# HW2schem.net
KiCad netlist of a schematic drawn in EAGLE
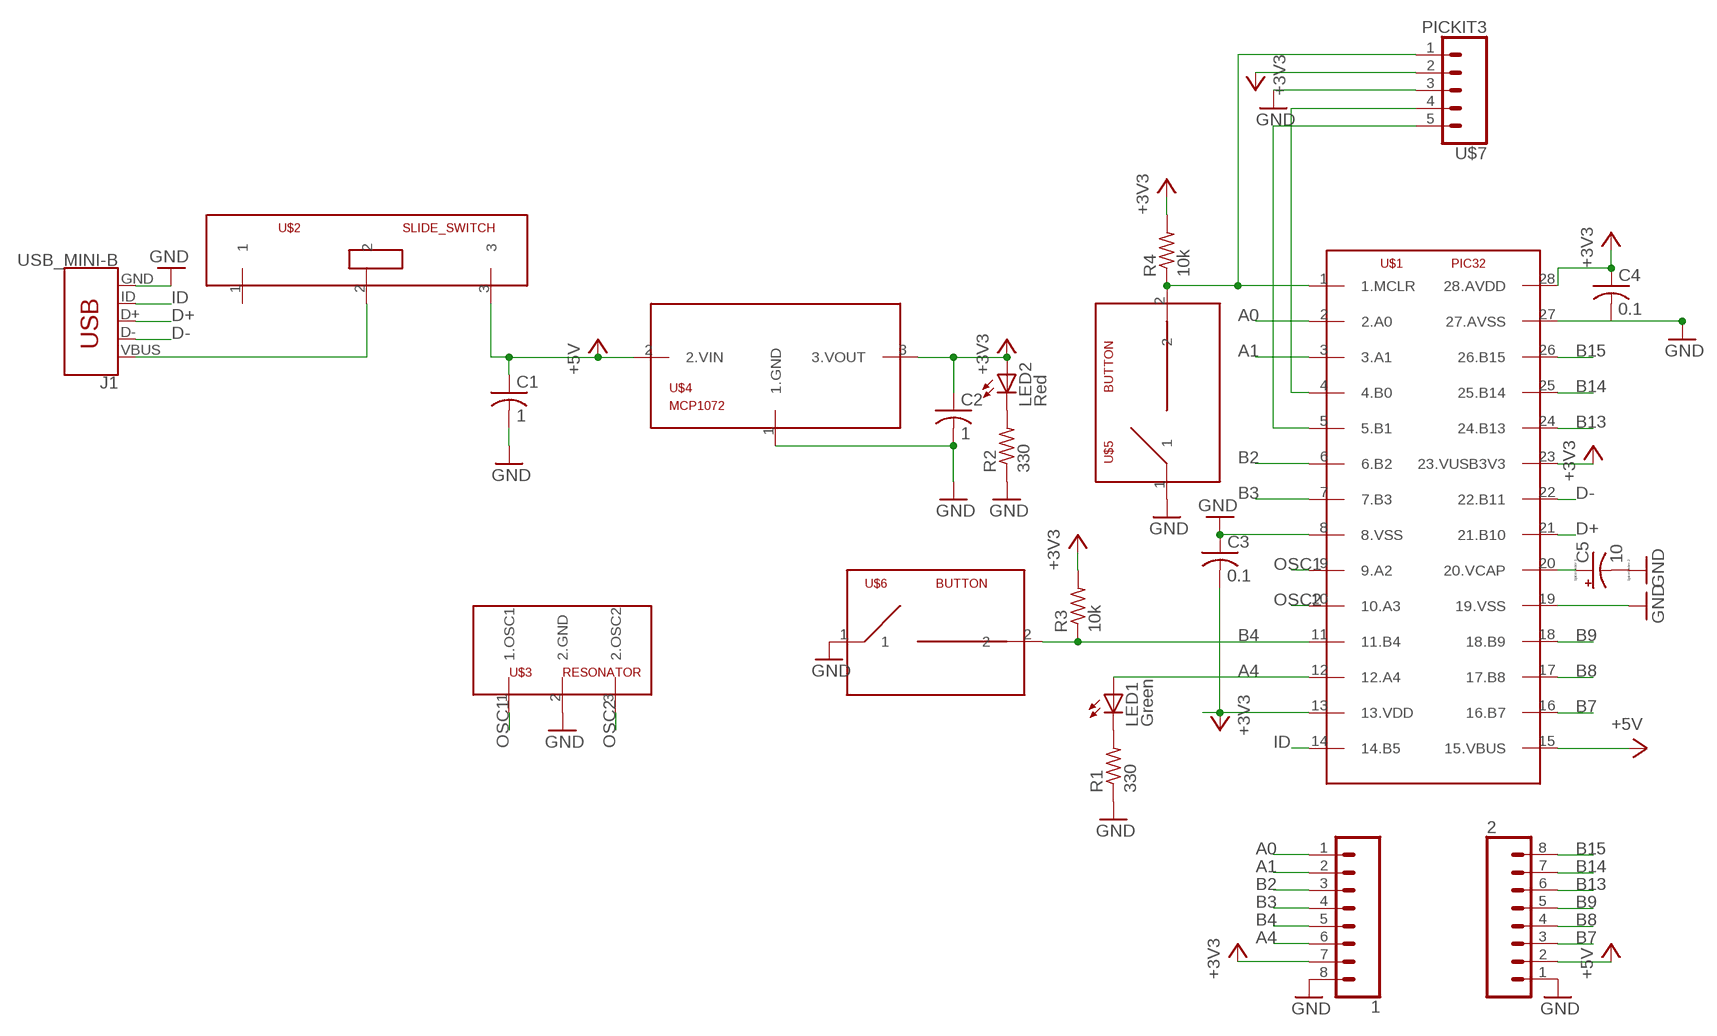
[diagram p0: schematic, sheet 1]

(export (version "E")
  (design (tool "Eeschema 10.0.6"))
  (components
    (comp (ref "1")
      (value "CONN_08NO_SILK_FEMALE_PTH")
      (footprint "eagle-import:1X08_NO_SILK")
      (libsource (lib "eagle-import") (part "CONN_08NO_SILK_FEMALE_PTH"))
    )
    (comp (ref "2")
      (value "CONN_08NO_SILK_FEMALE_PTH")
      (footprint "eagle-import:1X08_NO_SILK")
      (libsource (lib "eagle-import") (part "CONN_08NO_SILK_FEMALE_PTH"))
    )
    (comp (ref "C1")
      (value "1")
      (footprint "eagle-import:C025-024X044")
      (libsource (lib "eagle-import") (part "C-US025-024X044"))
    )
    (comp (ref "C2")
      (value "1")
      (footprint "eagle-import:C025-024X044")
      (libsource (lib "eagle-import") (part "C-US025-024X044"))
    )
    (comp (ref "C3")
      (value "0.1")
      (footprint "eagle-import:C025-024X044")
      (libsource (lib "eagle-import") (part "C-US025-024X044"))
    )
    (comp (ref "C4")
      (value "0.1")
      (footprint "eagle-import:C025-024X044")
      (libsource (lib "eagle-import") (part "C-US025-024X044"))
    )
    (comp (ref "C5")
      (value "10")
      (footprint "eagle-import:B45181A")
      (libsource (lib "eagle-import") (part "CPOL-USB45181A"))
    )
    (comp (ref "J1")
      (value "USB_MINI-B")
      (footprint "eagle-import:USB-MB-H")
      (libsource (lib "eagle-import") (part "USB_MINI-B"))
    )
    (comp (ref "LED1")
      (value "Green")
      (footprint "eagle-import:LED3MM")
      (libsource (lib "eagle-import") (part "LED3MM"))
    )
    (comp (ref "LED2")
      (value "Red")
      (footprint "eagle-import:LED3MM")
      (libsource (lib "eagle-import") (part "LED3MM"))
    )
    (comp (ref "R1")
      (value "330")
      (footprint "eagle-import:0204_7")
      (libsource (lib "eagle-import") (part "R-US_0204/7"))
    )
    (comp (ref "R2")
      (value "330")
      (footprint "eagle-import:0204_7")
      (libsource (lib "eagle-import") (part "R-US_0204/7"))
    )
    (comp (ref "R3")
      (value "10k")
      (footprint "eagle-import:0204_7")
      (libsource (lib "eagle-import") (part "R-US_0204/7"))
    )
    (comp (ref "R4")
      (value "10k")
      (footprint "eagle-import:0204_7")
      (libsource (lib "eagle-import") (part "R-US_0204/7"))
    )
    (comp (ref "U$1")
      (value "PIC32")
      (footprint "eagle-import:DIL28-3")
      (libsource (lib "eagle-import") (part "PIC32"))
    )
    (comp (ref "U$2")
      (value "SLIDE_SWITCH")
      (footprint "eagle-import:SLIDE_SWITCH")
      (libsource (lib "eagle-import") (part "SLIDE_SWITCH"))
    )
    (comp (ref "U$3")
      (value "RESONATOR")
      (footprint "eagle-import:RESONATOR")
      (libsource (lib "eagle-import") (part "RESONATOR"))
    )
    (comp (ref "U$4")
      (value "MCP1072")
      (footprint "eagle-import:TO92")
      (libsource (lib "eagle-import") (part "MCP1072"))
    )
    (comp (ref "U$5")
      (value "BUTTON")
      (footprint "eagle-import:BUTTON")
      (libsource (lib "eagle-import") (part "BUTTON"))
    )
    (comp (ref "U$6")
      (value "BUTTON")
      (footprint "eagle-import:BUTTON")
      (libsource (lib "eagle-import") (part "BUTTON"))
    )
    (comp (ref "U$7")
      (value "PICKIT3")
      (footprint "eagle-import:PICKIT3")
      (libsource (lib "eagle-import") (part "PICKIT3"))
    )
  )
  (nets
    (net (code "1") (name "+3V3") (class "Default")
      (node (ref "1") (pin "7") (pinfunction "7_7") (pintype "passive"))
      (node (ref "C2") (pin "1") (pinfunction "1_1") (pintype "passive"))
      (node (ref "C3") (pin "2") (pinfunction "2_2") (pintype "passive"))
      (node (ref "C4") (pin "1") (pinfunction "1_1") (pintype "passive"))
      (node (ref "LED2") (pin "A") (pinfunction "A_A") (pintype "passive"))
      (node (ref "R3") (pin "2") (pinfunction "2_2") (pintype "passive"))
      (node (ref "R4") (pin "2") (pinfunction "2_2") (pintype "passive"))
      (node (ref "U$1") (pin "13") (pinfunction "13.VDD_13") (pintype "bidirectional"))
      (node (ref "U$1") (pin "23") (pinfunction "23.VUSB3V3_23") (pintype "bidirectional"))
      (node (ref "U$1") (pin "28") (pinfunction "28.AVDD_28") (pintype "bidirectional"))
      (node (ref "U$4") (pin "3") (pinfunction "3.VOUT_3") (pintype "bidirectional"))
      (node (ref "U$7") (pin "2") (pinfunction "4.B0_2") (pintype "passive"))
    )
    (net (code "2") (name "+5V") (class "Default")
      (node (ref "2") (pin "2") (pinfunction "2_2") (pintype "passive"))
      (node (ref "C1") (pin "1") (pinfunction "1_1") (pintype "passive"))
      (node (ref "U$1") (pin "15") (pinfunction "15.VBUS_15") (pintype "bidirectional"))
      (node (ref "U$2") (pin "3") (pinfunction "3_3") (pintype "bidirectional"))
      (node (ref "U$4") (pin "2") (pinfunction "2.VIN_2") (pintype "bidirectional"))
    )
    (net (code "3") (name "/A0") (class "Default")
      (node (ref "1") (pin "1") (pinfunction "1_1") (pintype "passive"))
      (node (ref "U$1") (pin "2") (pinfunction "2.A0_2") (pintype "bidirectional"))
    )
    (net (code "4") (name "/A1") (class "Default")
      (node (ref "1") (pin "2") (pinfunction "2_2") (pintype "passive"))
      (node (ref "U$1") (pin "3") (pinfunction "3.A1_3") (pintype "bidirectional"))
    )
    (net (code "5") (name "/A4") (class "Default")
      (node (ref "1") (pin "6") (pinfunction "6_6") (pintype "passive"))
      (node (ref "LED1") (pin "A") (pinfunction "A_A") (pintype "passive"))
      (node (ref "U$1") (pin "12") (pinfunction "12.A4_12") (pintype "bidirectional"))
    )
    (net (code "6") (name "/B2") (class "Default")
      (node (ref "1") (pin "3") (pinfunction "3_3") (pintype "passive"))
      (node (ref "U$1") (pin "6") (pinfunction "6.B2_6") (pintype "bidirectional"))
    )
    (net (code "7") (name "/B3") (class "Default")
      (node (ref "1") (pin "4") (pinfunction "4_4") (pintype "passive"))
      (node (ref "U$1") (pin "7") (pinfunction "7.B3_7") (pintype "bidirectional"))
    )
    (net (code "8") (name "/B4") (class "Default")
      (node (ref "1") (pin "5") (pinfunction "5_5") (pintype "passive"))
      (node (ref "R3") (pin "1") (pinfunction "1_1") (pintype "passive"))
      (node (ref "U$1") (pin "11") (pinfunction "11.B4_11") (pintype "bidirectional"))
      (node (ref "U$6") (pin "2") (pinfunction "2_2") (pintype "bidirectional"))
    )
    (net (code "9") (name "/B7") (class "Default")
      (node (ref "2") (pin "3") (pinfunction "3_3") (pintype "passive"))
      (node (ref "U$1") (pin "16") (pinfunction "16.B7_16") (pintype "bidirectional"))
    )
    (net (code "10") (name "/B8") (class "Default")
      (node (ref "2") (pin "4") (pinfunction "4_4") (pintype "passive"))
      (node (ref "U$1") (pin "17") (pinfunction "17.B8_17") (pintype "bidirectional"))
    )
    (net (code "11") (name "/B9") (class "Default")
      (node (ref "2") (pin "5") (pinfunction "5_5") (pintype "passive"))
      (node (ref "U$1") (pin "18") (pinfunction "18.B9_18") (pintype "bidirectional"))
    )
    (net (code "12") (name "/B13") (class "Default")
      (node (ref "2") (pin "6") (pinfunction "6_6") (pintype "passive"))
      (node (ref "U$1") (pin "24") (pinfunction "24.B13_24") (pintype "bidirectional"))
    )
    (net (code "13") (name "/B14") (class "Default")
      (node (ref "2") (pin "7") (pinfunction "7_7") (pintype "passive"))
      (node (ref "U$1") (pin "25") (pinfunction "25.B14_25") (pintype "bidirectional"))
    )
    (net (code "14") (name "/B15") (class "Default")
      (node (ref "2") (pin "8") (pinfunction "8_8") (pintype "passive"))
      (node (ref "U$1") (pin "26") (pinfunction "26.B15_26") (pintype "bidirectional"))
    )
    (net (code "15") (name "/D+") (class "Default")
      (node (ref "J1") (pin "D+") (pinfunction "D+_D+") (pintype "bidirectional"))
      (node (ref "U$1") (pin "21") (pinfunction "21.B10_21") (pintype "bidirectional"))
    )
    (net (code "16") (name "/D-") (class "Default")
      (node (ref "J1") (pin "D-") (pinfunction "D-_D-") (pintype "bidirectional"))
      (node (ref "U$1") (pin "22") (pinfunction "22.B11_22") (pintype "bidirectional"))
    )
    (net (code "17") (name "/ID") (class "Default")
      (node (ref "J1") (pin "ID") (pinfunction "ID_ID") (pintype "bidirectional"))
      (node (ref "U$1") (pin "14") (pinfunction "14.B5_14") (pintype "bidirectional"))
    )
    (net (code "18") (name "/OSC1") (class "Default")
      (node (ref "U$1") (pin "9") (pinfunction "9.A2_9") (pintype "bidirectional"))
      (node (ref "U$3") (pin "1") (pinfunction "1.OSC1_1") (pintype "bidirectional"))
    )
    (net (code "19") (name "/OSC2") (class "Default")
      (node (ref "U$1") (pin "10") (pinfunction "10.A3_10") (pintype "bidirectional"))
      (node (ref "U$3") (pin "3") (pinfunction "2.OSC2_3") (pintype "bidirectional"))
    )
    (net (code "20") (name "GND") (class "Default")
      (node (ref "1") (pin "8") (pinfunction "8_8") (pintype "passive"))
      (node (ref "2") (pin "1") (pinfunction "1_1") (pintype "passive"))
      (node (ref "C1") (pin "2") (pinfunction "2_2") (pintype "passive"))
      (node (ref "C2") (pin "2") (pinfunction "2_2") (pintype "passive"))
      (node (ref "C3") (pin "1") (pinfunction "1_1") (pintype "passive"))
      (node (ref "C4") (pin "2") (pinfunction "2_2") (pintype "passive"))
      (node (ref "C5") (pin "-") (pinfunction "-_-") (pintype "passive"))
      (node (ref "J1") (pin "GND") (pinfunction "GND_GND") (pintype "power_in"))
      (node (ref "R1") (pin "1") (pinfunction "1_1") (pintype "passive"))
      (node (ref "R2") (pin "1") (pinfunction "1_1") (pintype "passive"))
      (node (ref "U$1") (pin "19") (pinfunction "19.VSS_19") (pintype "bidirectional"))
      (node (ref "U$1") (pin "27") (pinfunction "27.AVSS_27") (pintype "bidirectional"))
      (node (ref "U$1") (pin "8") (pinfunction "8.VSS_8") (pintype "bidirectional"))
      (node (ref "U$3") (pin "2") (pinfunction "2.GND_2") (pintype "bidirectional"))
      (node (ref "U$4") (pin "1") (pinfunction "1.GND_1") (pintype "bidirectional"))
      (node (ref "U$5") (pin "1") (pinfunction "1_1") (pintype "bidirectional"))
      (node (ref "U$6") (pin "1") (pinfunction "1_1") (pintype "bidirectional"))
      (node (ref "U$7") (pin "3") (pinfunction "3.GND_3") (pintype "passive"))
    )
    (net (code "21") (name "Net-(J1-PadVBUS)") (class "Default")
      (node (ref "J1") (pin "VBUS") (pinfunction "VBUS_VBUS") (pintype "power_in"))
      (node (ref "U$2") (pin "2") (pinfunction "2_2") (pintype "bidirectional"))
    )
    (net (code "22") (name "Net-(LED1-C)") (class "Default")
      (node (ref "LED1") (pin "K") (pinfunction "C_K") (pintype "passive"))
      (node (ref "R1") (pin "2") (pinfunction "2_2") (pintype "passive"))
    )
    (net (code "23") (name "Net-(LED2-C)") (class "Default")
      (node (ref "LED2") (pin "K") (pinfunction "C_K") (pintype "passive"))
      (node (ref "R2") (pin "2") (pinfunction "2_2") (pintype "passive"))
    )
    (net (code "24") (name "Net-(U$1-1.MCLR)") (class "Default")
      (node (ref "R4") (pin "1") (pinfunction "1_1") (pintype "passive"))
      (node (ref "U$1") (pin "1") (pinfunction "1.MCLR_1") (pintype "bidirectional"))
      (node (ref "U$5") (pin "2") (pinfunction "2_2") (pintype "bidirectional"))
      (node (ref "U$7") (pin "1") (pinfunction "5.B1_1") (pintype "passive"))
    )
    (net (code "25") (name "Net-(U$1-4.B0)") (class "Default")
      (node (ref "U$1") (pin "4") (pinfunction "4.B0_4") (pintype "bidirectional"))
      (node (ref "U$7") (pin "4") (pinfunction "2.VDD_4") (pintype "passive"))
    )
    (net (code "26") (name "Net-(U$1-5.B1)") (class "Default")
      (node (ref "U$1") (pin "5") (pinfunction "5.B1_5") (pintype "bidirectional"))
      (node (ref "U$7") (pin "5") (pinfunction "1.MCLR_5") (pintype "passive"))
    )
    (net (code "27") (name "Net-(U$1-20.VCAP)") (class "Default")
      (node (ref "C5") (pin "+") (pinfunction "+_+") (pintype "passive"))
      (node (ref "U$1") (pin "20") (pinfunction "20.VCAP_20") (pintype "bidirectional"))
    )
    (net (code "28") (name "unconnected-(U$2-Pad1)") (class "Default")
      (node (ref "U$2") (pin "1") (pinfunction "1_1") (pintype "bidirectional"))
    )
  )
)
